# Extension.net
KiCad netlist of a schematic drawn in Altium Designer
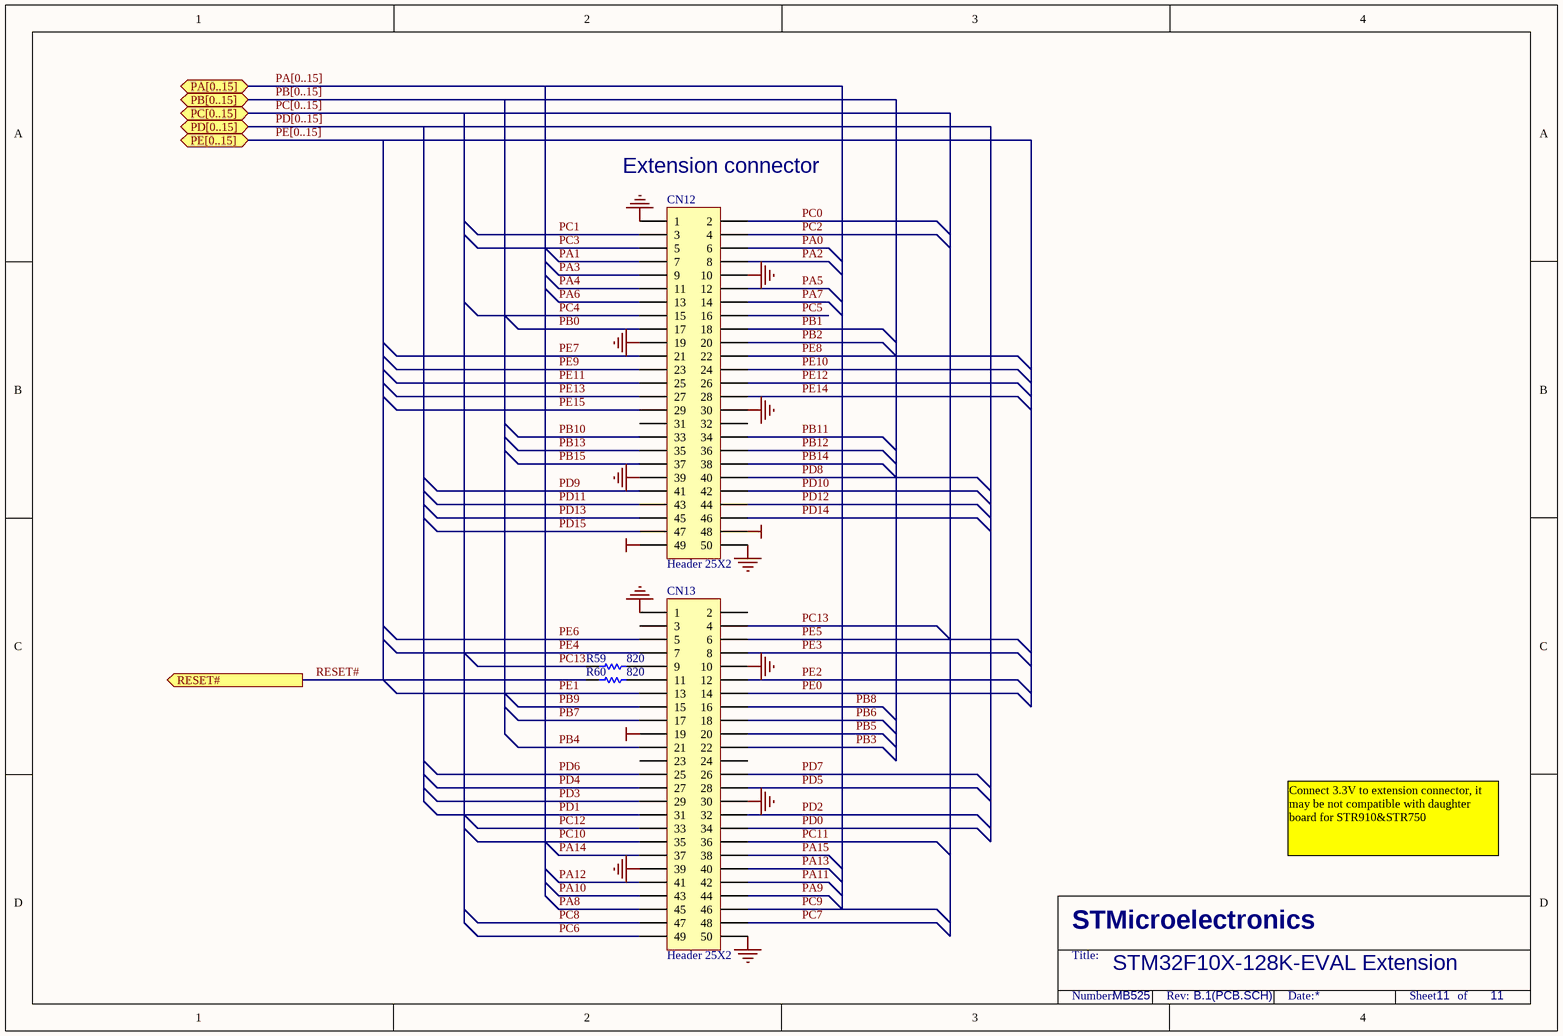
[diagram p0: Extension.SchDoc]

(export (version "E")
  (design (tool "Eeschema 10.0.6"))
  (components
    (comp (ref "CN12")
      (value "Header 25X2")
      (footprint "2*25P")
      (description "Header, 25-Pin, Dual row")
      (fields (field (name "PUBLISHER") "Altium Limited"))
      (libsource (lib "Miscellaneous Connectors") (part "Header 25X2"))
    )
    (comp (ref "CN13")
      (value "Header 25X2")
      (footprint "2*25P")
      (description "Header, 25-Pin, Dual row")
      (fields (field (name "PUBLISHER") "Altium Limited"))
      (libsource (lib "Miscellaneous Connectors") (part "Header 25X2"))
    )
    (comp (ref "R59")
      (value "820")
      (description "Resistor")
      (fields (field (name "PUBLISHER") "Altium Limited"))
      (libsource (lib "Miscellaneous Devices") (part "Res1"))
    )
    (comp (ref "R60")
      (value "820")
      (description "Resistor")
      (fields (field (name "PUBLISHER") "Altium Limited"))
      (libsource (lib "Miscellaneous Devices") (part "Res1"))
    )
  )
  (nets
    (net (code "3") (name "+3V3") (class "Default")
      (node (ref "CN12") (pin "48") (pinfunction "48_48") (pintype "passive"))
    )
    (net (code "4") (name "/PA0") (class "Default")
      (node (ref "CN12") (pin "6") (pinfunction "6_6") (pintype "passive"))
    )
    (net (code "5") (name "/PA1") (class "Default")
      (node (ref "CN12") (pin "7") (pinfunction "7_7") (pintype "passive"))
    )
    (net (code "6") (name "/PA2") (class "Default")
      (node (ref "CN12") (pin "8") (pinfunction "8_8") (pintype "passive"))
    )
    (net (code "7") (name "/PA3") (class "Default")
      (node (ref "CN12") (pin "9") (pinfunction "9_9") (pintype "passive"))
    )
    (net (code "8") (name "/PA4") (class "Default")
      (node (ref "CN12") (pin "11") (pinfunction "11_11") (pintype "passive"))
    )
    (net (code "9") (name "/PA5") (class "Default")
      (node (ref "CN12") (pin "12") (pinfunction "12_12") (pintype "passive"))
    )
    (net (code "10") (name "/PA6") (class "Default")
      (node (ref "CN12") (pin "13") (pinfunction "13_13") (pintype "passive"))
    )
    (net (code "11") (name "/PA7") (class "Default")
      (node (ref "CN12") (pin "14") (pinfunction "14_14") (pintype "passive"))
    )
    (net (code "12") (name "/PA8") (class "Default")
      (node (ref "CN13") (pin "45") (pinfunction "45_45") (pintype "passive"))
    )
    (net (code "13") (name "/PA9") (class "Default")
      (node (ref "CN13") (pin "44") (pinfunction "44_44") (pintype "passive"))
    )
    (net (code "14") (name "/PA10") (class "Default")
      (node (ref "CN13") (pin "43") (pinfunction "43_43") (pintype "passive"))
    )
    (net (code "15") (name "/PA11") (class "Default")
      (node (ref "CN13") (pin "42") (pinfunction "42_42") (pintype "passive"))
    )
    (net (code "16") (name "/PA12") (class "Default")
      (node (ref "CN13") (pin "41") (pinfunction "41_41") (pintype "passive"))
    )
    (net (code "17") (name "/PA13") (class "Default")
      (node (ref "CN13") (pin "40") (pinfunction "40_40") (pintype "passive"))
    )
    (net (code "18") (name "/PA14") (class "Default")
      (node (ref "CN13") (pin "37") (pinfunction "37_37") (pintype "passive"))
    )
    (net (code "19") (name "/PA15") (class "Default")
      (node (ref "CN13") (pin "38") (pinfunction "38_38") (pintype "passive"))
    )
    (net (code "21") (name "/PB0") (class "Default")
      (node (ref "CN12") (pin "17") (pinfunction "17_17") (pintype "passive"))
    )
    (net (code "22") (name "/PB1") (class "Default")
      (node (ref "CN12") (pin "18") (pinfunction "18_18") (pintype "passive"))
    )
    (net (code "23") (name "/PB2") (class "Default")
      (node (ref "CN12") (pin "20") (pinfunction "20_20") (pintype "passive"))
    )
    (net (code "24") (name "/PB3") (class "Default")
      (node (ref "CN13") (pin "22") (pinfunction "22_22") (pintype "passive"))
    )
    (net (code "25") (name "/PB4") (class "Default")
      (node (ref "CN13") (pin "21") (pinfunction "21_21") (pintype "passive"))
    )
    (net (code "26") (name "/PB5") (class "Default")
      (node (ref "CN13") (pin "20") (pinfunction "20_20") (pintype "passive"))
    )
    (net (code "27") (name "/PB6") (class "Default")
      (node (ref "CN13") (pin "18") (pinfunction "18_18") (pintype "passive"))
    )
    (net (code "28") (name "/PB7") (class "Default")
      (node (ref "CN13") (pin "17") (pinfunction "17_17") (pintype "passive"))
    )
    (net (code "29") (name "/PB8") (class "Default")
      (node (ref "CN13") (pin "16") (pinfunction "16_16") (pintype "passive"))
    )
    (net (code "30") (name "/PB9") (class "Default")
      (node (ref "CN13") (pin "15") (pinfunction "15_15") (pintype "passive"))
    )
    (net (code "31") (name "/PB10") (class "Default")
      (node (ref "CN12") (pin "33") (pinfunction "33_33") (pintype "passive"))
    )
    (net (code "32") (name "/PB11") (class "Default")
      (node (ref "CN12") (pin "34") (pinfunction "34_34") (pintype "passive"))
    )
    (net (code "33") (name "/PB12") (class "Default")
      (node (ref "CN12") (pin "36") (pinfunction "36_36") (pintype "passive"))
    )
    (net (code "34") (name "/PB13") (class "Default")
      (node (ref "CN12") (pin "35") (pinfunction "35_35") (pintype "passive"))
    )
    (net (code "35") (name "/PB14") (class "Default")
      (node (ref "CN12") (pin "38") (pinfunction "38_38") (pintype "passive"))
    )
    (net (code "36") (name "/PB15") (class "Default")
      (node (ref "CN12") (pin "37") (pinfunction "37_37") (pintype "passive"))
    )
    (net (code "38") (name "/PC0") (class "Default")
      (node (ref "CN12") (pin "2") (pinfunction "2_2") (pintype "passive"))
    )
    (net (code "39") (name "/PC1") (class "Default")
      (node (ref "CN12") (pin "3") (pinfunction "3_3") (pintype "passive"))
    )
    (net (code "40") (name "/PC2") (class "Default")
      (node (ref "CN12") (pin "4") (pinfunction "4_4") (pintype "passive"))
    )
    (net (code "41") (name "/PC3") (class "Default")
      (node (ref "CN12") (pin "5") (pinfunction "5_5") (pintype "passive"))
    )
    (net (code "42") (name "/PC4") (class "Default")
      (node (ref "CN12") (pin "15") (pinfunction "15_15") (pintype "passive"))
    )
    (net (code "43") (name "/PC5") (class "Default")
      (node (ref "CN12") (pin "16") (pinfunction "16_16") (pintype "passive"))
    )
    (net (code "44") (name "/PC6") (class "Default")
      (node (ref "CN13") (pin "49") (pinfunction "49_49") (pintype "passive"))
    )
    (net (code "45") (name "/PC7") (class "Default")
      (node (ref "CN13") (pin "48") (pinfunction "48_48") (pintype "passive"))
    )
    (net (code "46") (name "/PC8") (class "Default")
      (node (ref "CN13") (pin "47") (pinfunction "47_47") (pintype "passive"))
    )
    (net (code "47") (name "/PC9") (class "Default")
      (node (ref "CN13") (pin "46") (pinfunction "46_46") (pintype "passive"))
    )
    (net (code "48") (name "/PC10") (class "Default")
      (node (ref "CN13") (pin "35") (pinfunction "35_35") (pintype "passive"))
    )
    (net (code "49") (name "/PC11") (class "Default")
      (node (ref "CN13") (pin "36") (pinfunction "36_36") (pintype "passive"))
    )
    (net (code "50") (name "/PC12") (class "Default")
      (node (ref "CN13") (pin "33") (pinfunction "33_33") (pintype "passive"))
    )
    (net (code "51") (name "/PC13") (class "Default")
      (node (ref "CN13") (pin "4") (pinfunction "4_4") (pintype "passive"))
      (node (ref "R59") (pin "1") (pinfunction "1_1") (pintype "passive"))
    )
    (net (code "53") (name "/PD0") (class "Default")
      (node (ref "CN13") (pin "34") (pinfunction "34_34") (pintype "passive"))
    )
    (net (code "54") (name "/PD1") (class "Default")
      (node (ref "CN13") (pin "31") (pinfunction "31_31") (pintype "passive"))
    )
    (net (code "55") (name "/PD2") (class "Default")
      (node (ref "CN13") (pin "32") (pinfunction "32_32") (pintype "passive"))
    )
    (net (code "56") (name "/PD3") (class "Default")
      (node (ref "CN13") (pin "29") (pinfunction "29_29") (pintype "passive"))
    )
    (net (code "57") (name "/PD4") (class "Default")
      (node (ref "CN13") (pin "27") (pinfunction "27_27") (pintype "passive"))
    )
    (net (code "58") (name "/PD5") (class "Default")
      (node (ref "CN13") (pin "28") (pinfunction "28_28") (pintype "passive"))
    )
    (net (code "59") (name "/PD6") (class "Default")
      (node (ref "CN13") (pin "25") (pinfunction "25_25") (pintype "passive"))
    )
    (net (code "60") (name "/PD7") (class "Default")
      (node (ref "CN13") (pin "26") (pinfunction "26_26") (pintype "passive"))
    )
    (net (code "61") (name "/PD8") (class "Default")
      (node (ref "CN12") (pin "40") (pinfunction "40_40") (pintype "passive"))
    )
    (net (code "62") (name "/PD9") (class "Default")
      (node (ref "CN12") (pin "41") (pinfunction "41_41") (pintype "passive"))
    )
    (net (code "63") (name "/PD10") (class "Default")
      (node (ref "CN12") (pin "42") (pinfunction "42_42") (pintype "passive"))
    )
    (net (code "64") (name "/PD11") (class "Default")
      (node (ref "CN12") (pin "43") (pinfunction "43_43") (pintype "passive"))
    )
    (net (code "65") (name "/PD12") (class "Default")
      (node (ref "CN12") (pin "44") (pinfunction "44_44") (pintype "passive"))
    )
    (net (code "66") (name "/PD13") (class "Default")
      (node (ref "CN12") (pin "45") (pinfunction "45_45") (pintype "passive"))
    )
    (net (code "67") (name "/PD14") (class "Default")
      (node (ref "CN12") (pin "46") (pinfunction "46_46") (pintype "passive"))
    )
    (net (code "68") (name "/PD15") (class "Default")
      (node (ref "CN12") (pin "47") (pinfunction "47_47") (pintype "passive"))
    )
    (net (code "70") (name "/PE0") (class "Default")
      (node (ref "CN13") (pin "14") (pinfunction "14_14") (pintype "passive"))
    )
    (net (code "71") (name "/PE1") (class "Default")
      (node (ref "CN13") (pin "13") (pinfunction "13_13") (pintype "passive"))
    )
    (net (code "72") (name "/PE2") (class "Default")
      (node (ref "CN13") (pin "12") (pinfunction "12_12") (pintype "passive"))
    )
    (net (code "73") (name "/PE3") (class "Default")
      (node (ref "CN13") (pin "8") (pinfunction "8_8") (pintype "passive"))
    )
    (net (code "74") (name "/PE4") (class "Default")
      (node (ref "CN13") (pin "7") (pinfunction "7_7") (pintype "passive"))
    )
    (net (code "75") (name "/PE5") (class "Default")
      (node (ref "CN13") (pin "6") (pinfunction "6_6") (pintype "passive"))
    )
    (net (code "76") (name "/PE6") (class "Default")
      (node (ref "CN13") (pin "5") (pinfunction "5_5") (pintype "passive"))
    )
    (net (code "77") (name "/PE7") (class "Default")
      (node (ref "CN12") (pin "21") (pinfunction "21_21") (pintype "passive"))
    )
    (net (code "78") (name "/PE8") (class "Default")
      (node (ref "CN12") (pin "22") (pinfunction "22_22") (pintype "passive"))
    )
    (net (code "79") (name "/PE9") (class "Default")
      (node (ref "CN12") (pin "23") (pinfunction "23_23") (pintype "passive"))
    )
    (net (code "80") (name "/PE10") (class "Default")
      (node (ref "CN12") (pin "24") (pinfunction "24_24") (pintype "passive"))
    )
    (net (code "81") (name "/PE11") (class "Default")
      (node (ref "CN12") (pin "25") (pinfunction "25_25") (pintype "passive"))
    )
    (net (code "82") (name "/PE12") (class "Default")
      (node (ref "CN12") (pin "26") (pinfunction "26_26") (pintype "passive"))
    )
    (net (code "83") (name "/PE13") (class "Default")
      (node (ref "CN12") (pin "27") (pinfunction "27_27") (pintype "passive"))
    )
    (net (code "84") (name "/PE14") (class "Default")
      (node (ref "CN12") (pin "28") (pinfunction "28_28") (pintype "passive"))
    )
    (net (code "85") (name "/PE15") (class "Default")
      (node (ref "CN12") (pin "29") (pinfunction "29_29") (pintype "passive"))
    )
    (net (code "87") (name "/RESET#") (class "Default")
      (node (ref "R60") (pin "2") (pinfunction "2_2") (pintype "passive"))
    )
    (net (code "88") (name "D5V") (class "Default")
      (node (ref "CN12") (pin "49") (pinfunction "49_49") (pintype "passive"))
      (node (ref "CN13") (pin "19") (pinfunction "19_19") (pintype "passive"))
    )
    (net (code "89") (name "GND") (class "Default")
      (node (ref "CN12") (pin "1") (pinfunction "1_1") (pintype "passive"))
      (node (ref "CN12") (pin "10") (pinfunction "10_10") (pintype "passive"))
      (node (ref "CN12") (pin "19") (pinfunction "19_19") (pintype "passive"))
      (node (ref "CN12") (pin "30") (pinfunction "30_30") (pintype "passive"))
      (node (ref "CN12") (pin "39") (pinfunction "39_39") (pintype "passive"))
      (node (ref "CN12") (pin "50") (pinfunction "50_50") (pintype "passive"))
      (node (ref "CN13") (pin "1") (pinfunction "1_1") (pintype "passive"))
      (node (ref "CN13") (pin "10") (pinfunction "10_10") (pintype "passive"))
      (node (ref "CN13") (pin "30") (pinfunction "30_30") (pintype "passive"))
      (node (ref "CN13") (pin "39") (pinfunction "39_39") (pintype "passive"))
      (node (ref "CN13") (pin "50") (pinfunction "50_50") (pintype "passive"))
    )
    (net (code "90") (name "Net-(CN13-Pad9)") (class "Default")
      (node (ref "CN13") (pin "9") (pinfunction "9_9") (pintype "passive"))
      (node (ref "R59") (pin "2") (pinfunction "2_2") (pintype "passive"))
    )
    (net (code "91") (name "Net-(CN13-Pad11)") (class "Default")
      (node (ref "CN13") (pin "11") (pinfunction "11_11") (pintype "passive"))
      (node (ref "R60") (pin "1") (pinfunction "1_1") (pintype "passive"))
    )
    (net (code "92") (name "unconnected-(CN12-Pad31)") (class "Default")
      (node (ref "CN12") (pin "31") (pinfunction "31_31") (pintype "passive"))
    )
    (net (code "93") (name "unconnected-(CN12-Pad32)") (class "Default")
      (node (ref "CN12") (pin "32") (pinfunction "32_32") (pintype "passive"))
    )
    (net (code "94") (name "unconnected-(CN13-Pad2)") (class "Default")
      (node (ref "CN13") (pin "2") (pinfunction "2_2") (pintype "passive"))
    )
    (net (code "95") (name "unconnected-(CN13-Pad3)") (class "Default")
      (node (ref "CN13") (pin "3") (pinfunction "3_3") (pintype "passive"))
    )
    (net (code "96") (name "unconnected-(CN13-Pad23)") (class "Default")
      (node (ref "CN13") (pin "23") (pinfunction "23_23") (pintype "passive"))
    )
    (net (code "97") (name "unconnected-(CN13-Pad24)") (class "Default")
      (node (ref "CN13") (pin "24") (pinfunction "24_24") (pintype "passive"))
    )
  )
)
